# onStep-board-uc.net
KiCad netlist of a schematic drawn in Altium Designer
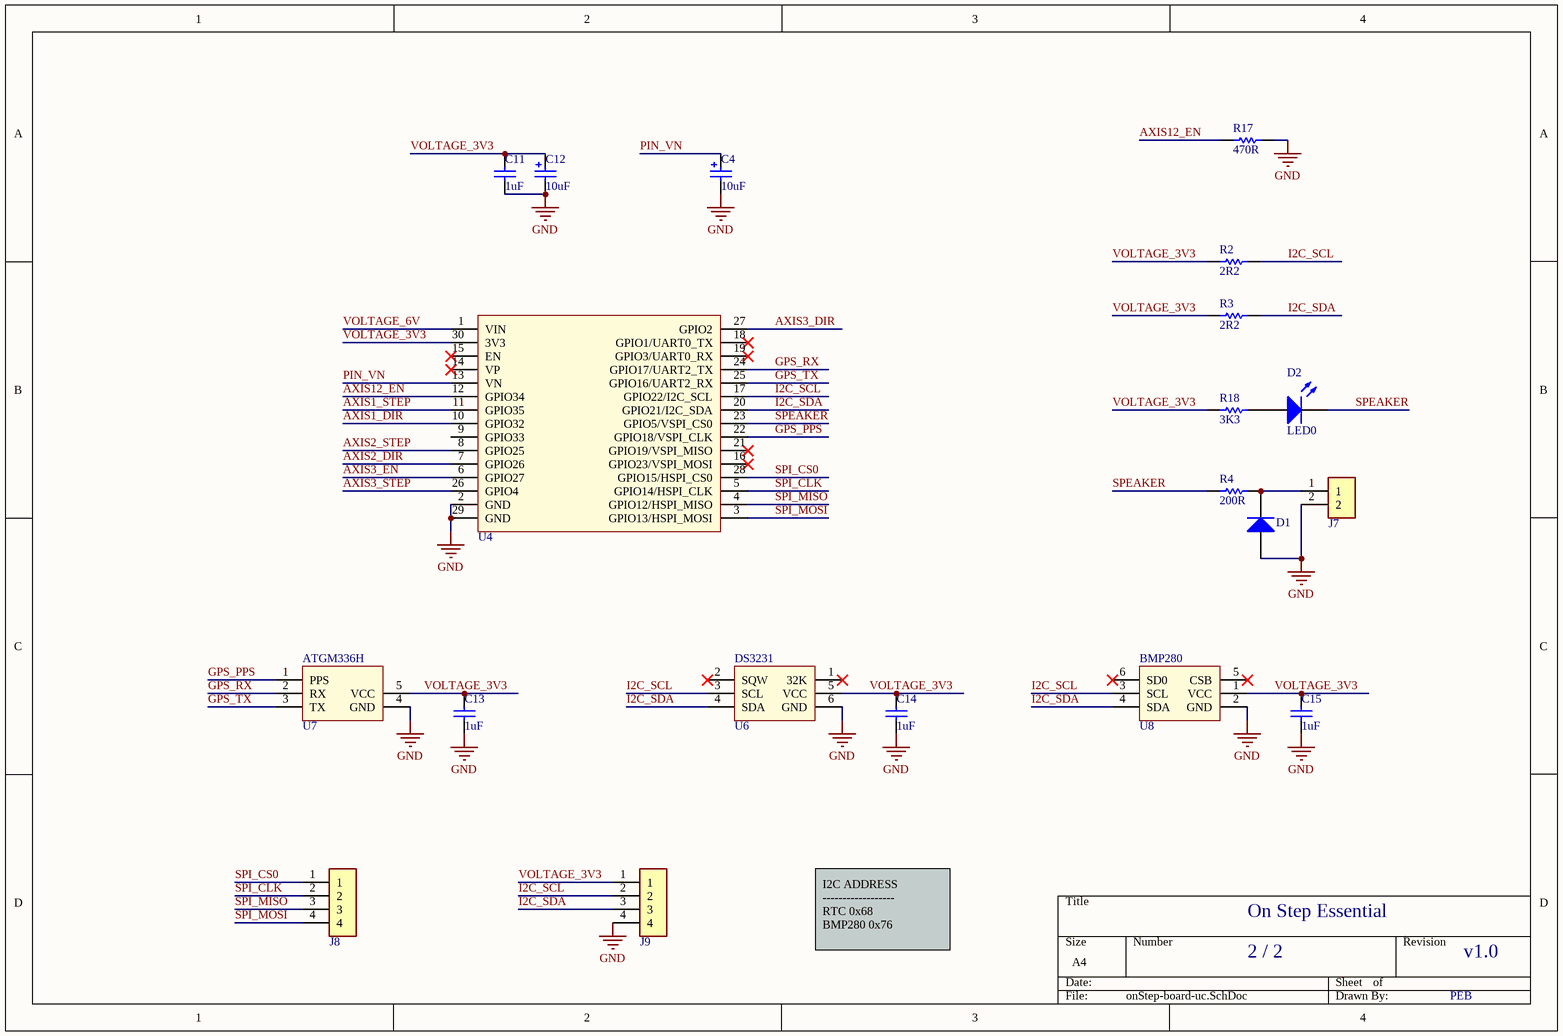
[diagram p0: onStep-board-uc.SchDoc]

(export (version "E")
  (design (tool "Eeschema 10.0.6"))
  (components
    (comp (ref "C4")
      (value "10uF")
      (footprint "WCAP-ASLL_5x5.5")
      (description "WCAP-ASLL Aluminum Electrolytic Capacitors, size Ф8x10.5mm, 25V DC, 150uF")
      (fields (field (name "PART NUMBER") "865060453006") (field (name "PUBLISHER") "Wurth Elektronik"))
      (libsource (lib "ALTIUM-WCAP-ASLL-rev17a") (part "865060453006"))
    )
    (comp (ref "C11")
      (value "1uF")
      (footprint "0805")
      (description "Capacitor")
      (fields (field (name "Comment") "Cap") (field (name "PUBLISHER") "Altium Limited"))
      (libsource (lib "Miscellaneous Devices") (part "Cap"))
    )
    (comp (ref "C12")
      (value "10uF")
      (footprint "WCAP-ASLL_8x10.5")
      (description "WCAP-ASLL Aluminum Electrolytic Capacitors, size Ф8x10.5mm, 25V DC, 150uF")
      (fields (field (name "PART NUMBER") "865060453006") (field (name "PUBLISHER") "Wurth Elektronik"))
      (libsource (lib "ALTIUM-WCAP-ASLL-rev17a") (part "865060453006"))
    )
    (comp (ref "C13")
      (value "1uF")
      (footprint "0805")
      (description "Capacitor")
      (fields (field (name "Comment") "Cap") (field (name "PUBLISHER") "Altium Limited"))
      (libsource (lib "Miscellaneous Devices") (part "Cap"))
    )
    (comp (ref "C14")
      (value "1uF")
      (footprint "0805")
      (description "Capacitor")
      (fields (field (name "Comment") "Cap") (field (name "PUBLISHER") "Altium Limited"))
      (libsource (lib "Miscellaneous Devices") (part "Cap"))
    )
    (comp (ref "C15")
      (value "1uF")
      (footprint "0805")
      (description "Capacitor")
      (fields (field (name "Comment") "Cap") (field (name "PUBLISHER") "Altium Limited"))
      (libsource (lib "Miscellaneous Devices") (part "Cap"))
    )
    (comp (ref "D1")
      (value "Diode")
      (footprint "SMC")
      (description "Default Diode")
      (fields (field (name "PUBLISHER") "Altium Limited"))
      (libsource (lib "Miscellaneous Devices") (part "Diode"))
    )
    (comp (ref "D2")
      (value "LED0")
      (footprint "LED-0")
      (description "Typical INFRARED GaAs LED")
      (fields (field (name "PUBLISHER") "Altium Limited"))
      (libsource (lib "Miscellaneous Devices") (part "LED0"))
    )
    (comp (ref "J7")
      (value "SPEAKER")
      (footprint "lib_common:B2BXHALFSN")
      (description "Connector")
      (fields (field (name "MANUFACTURER_PART_NUMBER") "B2B-XH-A(LF)(SN)"))
      (libsource (lib "lib_common") (part "B2B-XH-A_LF__SN_"))
    )
    (comp (ref "J8")
      (value "SPI")
      (footprint "p4")
      (description "Connector")
      (fields (field (name "MANUFACTURER_PART_NUMBER") "B4B-XH-A(LF)(SN)"))
      (libsource (lib "lib_common") (part "B4B-XH-A_LF__SN_"))
    )
    (comp (ref "J9")
      (value "I2C")
      (footprint "p4")
      (description "Connector")
      (fields (field (name "MANUFACTURER_PART_NUMBER") "B4B-XH-A(LF)(SN)"))
      (libsource (lib "lib_common") (part "B4B-XH-A_LF__SN_"))
    )
    (comp (ref "R2")
      (value "2R2")
      (footprint "0805")
      (description "Resistor")
      (fields (field (name "Comment") "Res1") (field (name "PUBLISHER") "Altium Limited"))
      (libsource (lib "Miscellaneous Devices") (part "Res1"))
    )
    (comp (ref "R3")
      (value "2R2")
      (footprint "0805")
      (description "Resistor")
      (fields (field (name "Comment") "Res1") (field (name "PUBLISHER") "Altium Limited"))
      (libsource (lib "Miscellaneous Devices") (part "Res1"))
    )
    (comp (ref "R4")
      (value "200R")
      (footprint "0805")
      (description "Resistor")
      (fields (field (name "Comment") "Res1") (field (name "PUBLISHER") "Altium Limited"))
      (libsource (lib "Miscellaneous Devices") (part "Res1"))
    )
    (comp (ref "R17")
      (value "470R")
      (footprint "0805")
      (description "Resistor")
      (fields (field (name "Comment") "Res1") (field (name "PUBLISHER") "Altium Limited"))
      (libsource (lib "Miscellaneous Devices") (part "Res1"))
    )
    (comp (ref "R18")
      (value "3K3")
      (footprint "0805")
      (description "Resistor")
      (fields (field (name "Comment") "Res1") (field (name "PUBLISHER") "Altium Limited"))
      (libsource (lib "Miscellaneous Devices") (part "Res1"))
    )
    (comp (ref "U4")
      (value "ESP32-WROOM-DEVKIT")
      (footprint "ESP32-WROOM-DEVKIT")
      (libsource (lib "lib_common") (part "ESP32-WROOM-DEVKIT"))
    )
    (comp (ref "U6") (value "DS3231") (footprint "DS3231") (libsource (lib "lib_common") (part "DS3231")))
    (comp (ref "U7")
      (value "ATGM336H")
      (footprint "ATGM336H")
      (libsource (lib "lib_common") (part "ATGM336H"))
    )
    (comp (ref "U8") (value "BMP280") (footprint "BMP280") (libsource (lib "lib_common") (part "BMP280")))
  )
  (nets
    (net (code "1") (name "/AXIS1_DIR") (class "Default")
      (node (ref "U4") (pin "10") (pinfunction "GPIO32_10") (pintype "passive"))
    )
    (net (code "2") (name "/AXIS1_STEP") (class "Default")
      (node (ref "U4") (pin "11") (pinfunction "GPIO35_11") (pintype "passive"))
    )
    (net (code "3") (name "/AXIS2_DIR") (class "Default")
      (node (ref "U4") (pin "7") (pinfunction "GPIO26_7") (pintype "passive"))
    )
    (net (code "4") (name "/AXIS2_STEP") (class "Default")
      (node (ref "U4") (pin "8") (pinfunction "GPIO25_8") (pintype "passive"))
    )
    (net (code "5") (name "/AXIS3_DIR") (class "Default")
      (node (ref "U4") (pin "27") (pinfunction "GPIO2_27") (pintype "passive"))
    )
    (net (code "6") (name "/AXIS3_EN") (class "Default")
      (node (ref "U4") (pin "6") (pinfunction "GPIO27_6") (pintype "passive"))
    )
    (net (code "7") (name "/AXIS3_STEP") (class "Default")
      (node (ref "U4") (pin "26") (pinfunction "GPIO4_26") (pintype "passive"))
    )
    (net (code "8") (name "/AXIS12_EN") (class "Default")
      (node (ref "R17") (pin "2") (pinfunction "2_2") (pintype "passive"))
      (node (ref "U4") (pin "12") (pinfunction "GPIO34_12") (pintype "passive"))
    )
    (net (code "9") (name "/GPS_PPS") (class "Default")
      (node (ref "U4") (pin "22") (pinfunction "GPIO18/VSPI_CLK_22") (pintype "passive"))
      (node (ref "U7") (pin "1") (pinfunction "PPS_1") (pintype "passive"))
    )
    (net (code "10") (name "/GPS_RX") (class "Default")
      (node (ref "U4") (pin "24") (pinfunction "GPIO17/UART2_TX_24") (pintype "passive"))
      (node (ref "U7") (pin "2") (pinfunction "RX_2") (pintype "passive"))
    )
    (net (code "11") (name "/GPS_TX") (class "Default")
      (node (ref "U4") (pin "25") (pinfunction "GPIO16/UART2_RX_25") (pintype "passive"))
      (node (ref "U7") (pin "3") (pinfunction "TX_3") (pintype "passive"))
    )
    (net (code "12") (name "/I2C_SCL") (class "Default")
      (node (ref "J9") (pin "2") (pinfunction "2_2") (pintype "passive"))
      (node (ref "R2") (pin "1") (pinfunction "1_1") (pintype "passive"))
      (node (ref "U4") (pin "17") (pinfunction "GPIO22/I2C_SCL_17") (pintype "passive"))
      (node (ref "U6") (pin "3") (pinfunction "SCL_3") (pintype "passive"))
      (node (ref "U8") (pin "3") (pinfunction "SCL_3") (pintype "passive"))
    )
    (net (code "13") (name "/I2C_SDA") (class "Default")
      (node (ref "J9") (pin "3") (pinfunction "3_3") (pintype "passive"))
      (node (ref "R3") (pin "1") (pinfunction "1_1") (pintype "passive"))
      (node (ref "U4") (pin "20") (pinfunction "GPIO21/I2C_SDA_20") (pintype "passive"))
      (node (ref "U6") (pin "4") (pinfunction "SDA_4") (pintype "passive"))
      (node (ref "U8") (pin "4") (pinfunction "SDA_4") (pintype "passive"))
    )
    (net (code "14") (name "/PIN_VN") (class "Default")
      (node (ref "C4") (pin "1") (pinfunction "P_1") (pintype "passive"))
      (node (ref "U4") (pin "13") (pinfunction "VN_13") (pintype "passive"))
    )
    (net (code "15") (name "/SPEAKER") (class "Default")
      (node (ref "D2") (pin "2") (pinfunction "K_2") (pintype "passive"))
      (node (ref "R4") (pin "2") (pinfunction "2_2") (pintype "passive"))
      (node (ref "U4") (pin "23") (pinfunction "GPIO5/VSPI_CS0_23") (pintype "passive"))
    )
    (net (code "16") (name "/SPI_CLK") (class "Default")
      (node (ref "J8") (pin "2") (pinfunction "2_2") (pintype "passive"))
      (node (ref "U4") (pin "5") (pinfunction "GPIO14/HSPI_CLK_5") (pintype "passive"))
    )
    (net (code "17") (name "/SPI_CS0") (class "Default")
      (node (ref "J8") (pin "1") (pinfunction "1_1") (pintype "passive"))
      (node (ref "U4") (pin "28") (pinfunction "GPIO15/HSPI_CS0_28") (pintype "passive"))
    )
    (net (code "18") (name "/SPI_MISO") (class "Default")
      (node (ref "J8") (pin "3") (pinfunction "3_3") (pintype "passive"))
      (node (ref "U4") (pin "4") (pinfunction "GPIO12/HSPI_MISO_4") (pintype "passive"))
    )
    (net (code "19") (name "/SPI_MOSI") (class "Default")
      (node (ref "J8") (pin "4") (pinfunction "4_4") (pintype "passive"))
      (node (ref "U4") (pin "3") (pinfunction "GPIO13/HSPI_MOSI_3") (pintype "passive"))
    )
    (net (code "20") (name "/VOLTAGE_3V3") (class "Default")
      (node (ref "C11") (pin "2") (pinfunction "2_2") (pintype "passive"))
      (node (ref "C12") (pin "1") (pinfunction "P_1") (pintype "passive"))
      (node (ref "C13") (pin "2") (pinfunction "2_2") (pintype "passive"))
      (node (ref "C14") (pin "2") (pinfunction "2_2") (pintype "passive"))
      (node (ref "C15") (pin "2") (pinfunction "2_2") (pintype "passive"))
      (node (ref "J9") (pin "1") (pinfunction "1_1") (pintype "passive"))
      (node (ref "R18") (pin "2") (pinfunction "2_2") (pintype "passive"))
      (node (ref "R2") (pin "2") (pinfunction "2_2") (pintype "passive"))
      (node (ref "R3") (pin "2") (pinfunction "2_2") (pintype "passive"))
      (node (ref "U4") (pin "30") (pinfunction "3V3_30") (pintype "passive"))
      (node (ref "U6") (pin "5") (pinfunction "VCC_5") (pintype "passive"))
      (node (ref "U7") (pin "5") (pinfunction "VCC_5") (pintype "passive"))
      (node (ref "U8") (pin "1") (pinfunction "VCC_1") (pintype "passive"))
    )
    (net (code "21") (name "/VOLTAGE_6V") (class "Default")
      (node (ref "U4") (pin "1") (pinfunction "VIN_1") (pintype "passive"))
    )
    (net (code "22") (name "GND") (class "Default")
      (node (ref "C11") (pin "1") (pinfunction "1_1") (pintype "passive"))
      (node (ref "C12") (pin "2") (pinfunction "N_2") (pintype "passive"))
      (node (ref "C13") (pin "1") (pinfunction "1_1") (pintype "passive"))
      (node (ref "C14") (pin "1") (pinfunction "1_1") (pintype "passive"))
      (node (ref "C15") (pin "1") (pinfunction "1_1") (pintype "passive"))
      (node (ref "C4") (pin "2") (pinfunction "N_2") (pintype "passive"))
      (node (ref "D1") (pin "1") (pinfunction "A_1") (pintype "passive"))
      (node (ref "J7") (pin "2") (pinfunction "2_2") (pintype "passive"))
      (node (ref "J9") (pin "4") (pinfunction "4_4") (pintype "passive"))
      (node (ref "R17") (pin "1") (pinfunction "1_1") (pintype "passive"))
      (node (ref "U4") (pin "2") (pinfunction "GND_2") (pintype "passive"))
      (node (ref "U4") (pin "29") (pinfunction "GND_29") (pintype "passive"))
      (node (ref "U6") (pin "6") (pinfunction "GND_6") (pintype "passive"))
      (node (ref "U7") (pin "4") (pinfunction "GND_4") (pintype "passive"))
      (node (ref "U8") (pin "2") (pinfunction "GND_2") (pintype "passive"))
    )
    (net (code "23") (name "Net-(D1-K)") (class "Default")
      (node (ref "D1") (pin "2") (pinfunction "K_2") (pintype "passive"))
      (node (ref "J7") (pin "1") (pinfunction "1_1") (pintype "passive"))
      (node (ref "R4") (pin "1") (pinfunction "1_1") (pintype "passive"))
    )
    (net (code "24") (name "Net-(D2-A)") (class "Default")
      (node (ref "D2") (pin "1") (pinfunction "A_1") (pintype "passive"))
      (node (ref "R18") (pin "1") (pinfunction "1_1") (pintype "passive"))
    )
    (net (code "25") (name "unconnected-(U4-EN-Pad15)") (class "Default")
      (node (ref "U4") (pin "15") (pinfunction "EN_15") (pintype "passive+no_connect"))
    )
    (net (code "26") (name "unconnected-(U4-GPIO1{slash}UART0_TX-Pad18)") (class "Default")
      (node (ref "U4") (pin "18") (pinfunction "GPIO1/UART0_TX_18") (pintype "passive+no_connect"))
    )
    (net (code "27") (name "unconnected-(U4-GPIO3{slash}UART0_RX-Pad19)") (class "Default")
      (node (ref "U4") (pin "19") (pinfunction "GPIO3/UART0_RX_19") (pintype "passive+no_connect"))
    )
    (net (code "28") (name "unconnected-(U4-GPIO19{slash}VSPI_MISO-Pad21)") (class "Default")
      (node (ref "U4") (pin "21") (pinfunction "GPIO19/VSPI_MISO_21") (pintype "passive+no_connect"))
    )
    (net (code "29") (name "unconnected-(U4-GPIO23{slash}VSPI_MOSI-Pad16)") (class "Default")
      (node (ref "U4") (pin "16") (pinfunction "GPIO23/VSPI_MOSI_16") (pintype "passive+no_connect"))
    )
    (net (code "30") (name "unconnected-(U4-GPIO33-Pad9)") (class "Default")
      (node (ref "U4") (pin "9") (pinfunction "GPIO33_9") (pintype "passive"))
    )
    (net (code "31") (name "unconnected-(U4-VP-Pad14)") (class "Default")
      (node (ref "U4") (pin "14") (pinfunction "VP_14") (pintype "passive+no_connect"))
    )
    (net (code "32") (name "unconnected-(U6-32K-Pad1)") (class "Default")
      (node (ref "U6") (pin "1") (pinfunction "32K_1") (pintype "passive+no_connect"))
    )
    (net (code "33") (name "unconnected-(U6-SQW-Pad2)") (class "Default")
      (node (ref "U6") (pin "2") (pinfunction "SQW_2") (pintype "passive+no_connect"))
    )
    (net (code "34") (name "unconnected-(U8-CSB-Pad5)") (class "Default")
      (node (ref "U8") (pin "5") (pinfunction "CSB_5") (pintype "passive+no_connect"))
    )
    (net (code "35") (name "unconnected-(U8-SD0-Pad6)") (class "Default")
      (node (ref "U8") (pin "6") (pinfunction "SD0_6") (pintype "passive+no_connect"))
    )
  )
)
